# Keg_Cop_-_RJ45.net
KiCad netlist of a schematic drawn in EAGLE
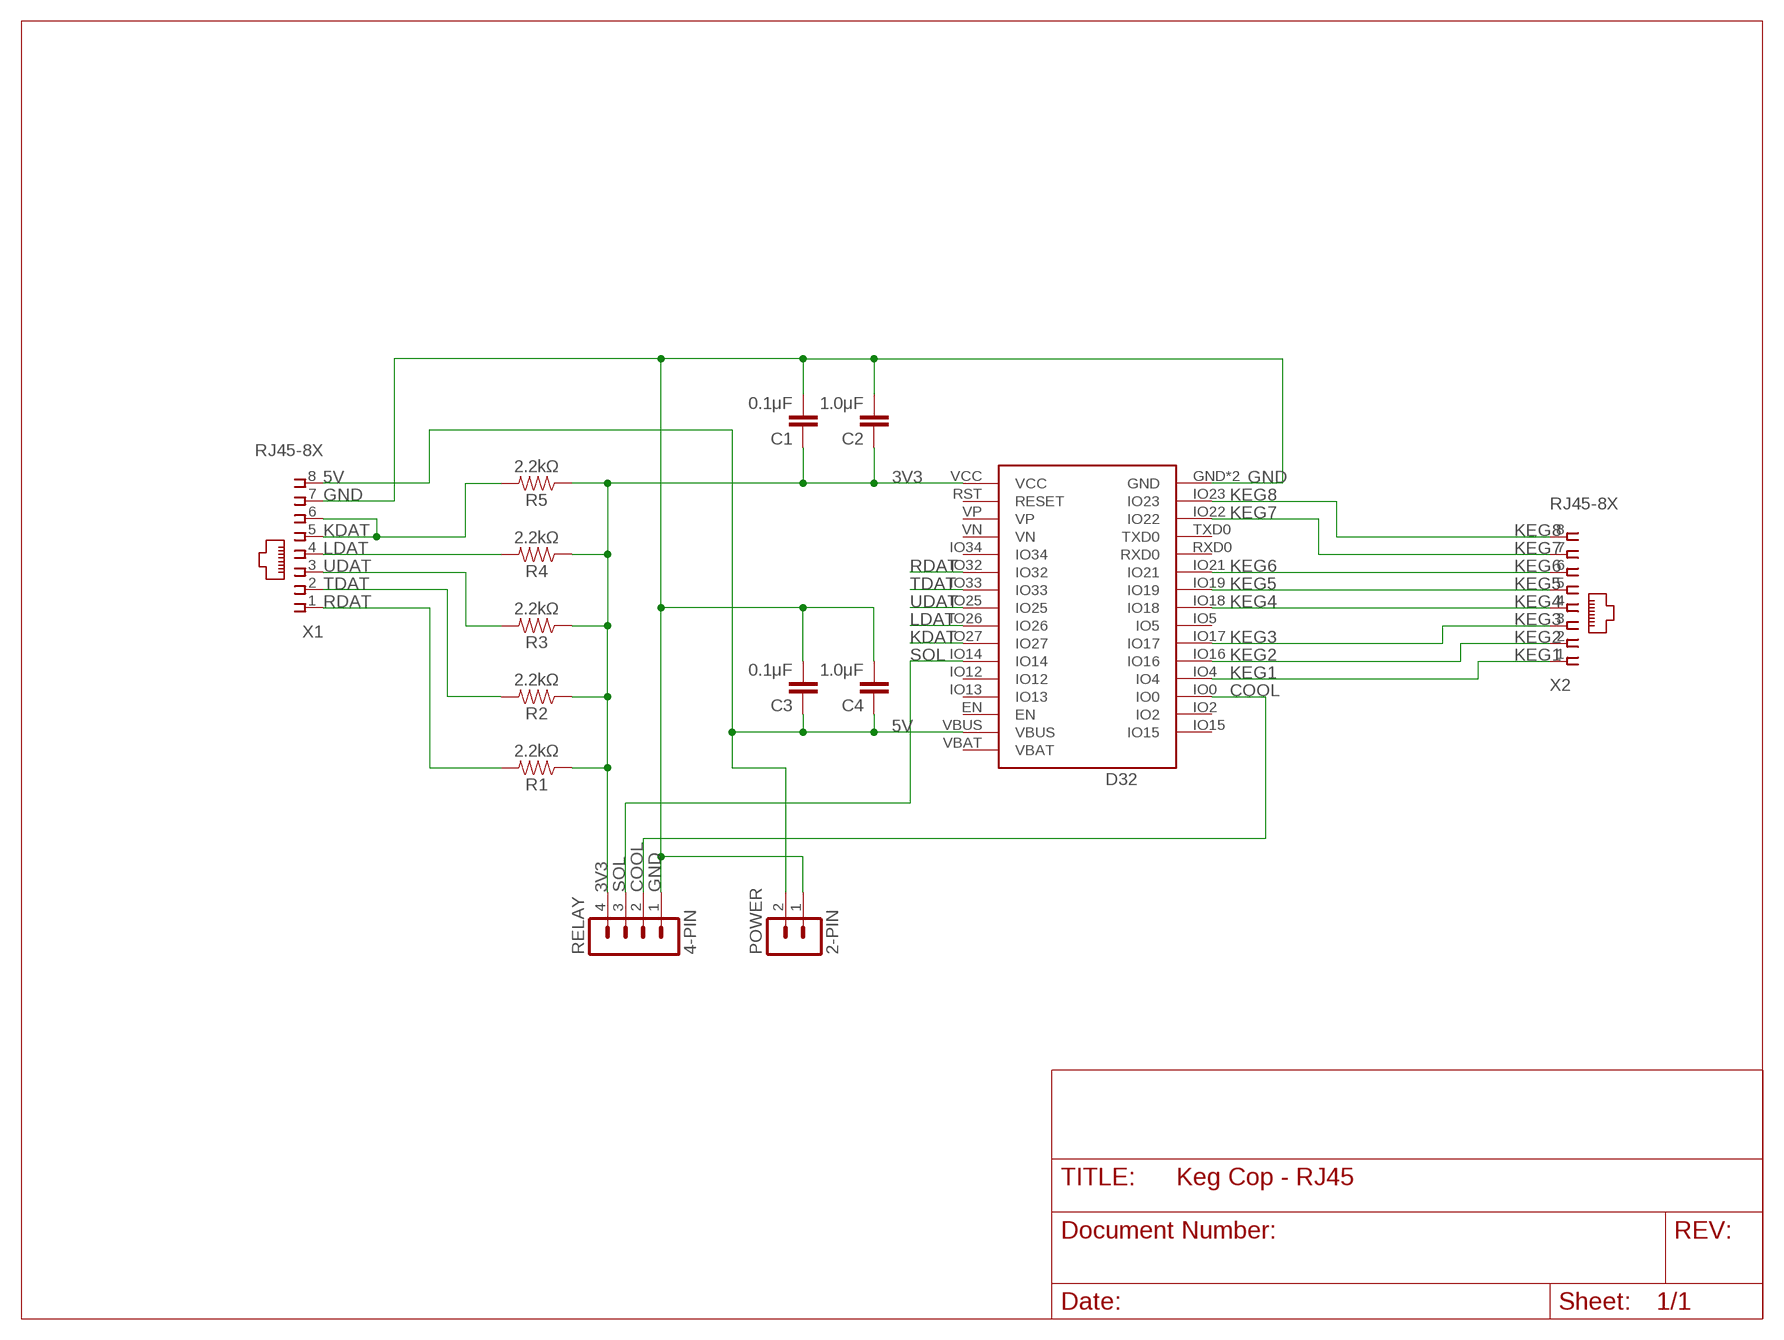
[diagram p0: schematic, sheet 1]

(export (version "E")
  (design (tool "Eeschema 10.0.6"))
  (components
    (comp (ref "C1")
      (value "0.1μF")
      (footprint "eagle-import:CAP_PTH-2.54")
      (libsource (lib "eagle-import") (part "CAP_CERAMIC_2.54"))
    )
    (comp (ref "C2")
      (value "1.0μF")
      (footprint "eagle-import:CAP_PTH-2.54")
      (libsource (lib "eagle-import") (part "CAP_CERAMIC_2.54"))
    )
    (comp (ref "C3")
      (value "0.1μF")
      (footprint "eagle-import:CAP_PTH-2.54")
      (libsource (lib "eagle-import") (part "CAP_CERAMIC_2.54"))
    )
    (comp (ref "C4")
      (value "1.0μF")
      (footprint "eagle-import:CAP_PTH-2.54")
      (libsource (lib "eagle-import") (part "CAP_CERAMIC_2.54"))
    )
    (comp (ref "D32")
      (value "Lolin D32")
      (footprint "eagle-import:D32_NO_BATT")
      (libsource (lib "eagle-import") (part "WEMOS-D32D32_NO_BATT"))
    )
    (comp (ref "POWER")
      (value "2-PIN")
      (footprint "eagle-import:HDR-2_VERT")
      (libsource (lib "eagle-import") (part "HDR-2"))
    )
    (comp (ref "R1")
      (value "2.2kΩ")
      (footprint "eagle-import:AXIAL-0.3")
      (libsource (lib "eagle-import") (part "RESISTORAXIAL-0.3"))
    )
    (comp (ref "R2")
      (value "2.2kΩ")
      (footprint "eagle-import:AXIAL-0.3")
      (libsource (lib "eagle-import") (part "RESISTORAXIAL-0.3"))
    )
    (comp (ref "R3")
      (value "2.2kΩ")
      (footprint "eagle-import:AXIAL-0.3")
      (libsource (lib "eagle-import") (part "RESISTORAXIAL-0.3"))
    )
    (comp (ref "R4")
      (value "2.2kΩ")
      (footprint "eagle-import:AXIAL-0.3")
      (libsource (lib "eagle-import") (part "RESISTORAXIAL-0.3"))
    )
    (comp (ref "R5")
      (value "2.2kΩ")
      (footprint "eagle-import:AXIAL-0.3")
      (libsource (lib "eagle-import") (part "RESISTORAXIAL-0.3"))
    )
    (comp (ref "RELAY")
      (value "4-PIN")
      (footprint "eagle-import:MA04-1")
      (libsource (lib "eagle-import") (part "MA04-1"))
    )
    (comp (ref "X1")
      (value "RJ45-8X")
      (footprint "eagle-import:RJ45-NO-SHIELD")
      (libsource (lib "eagle-import") (part "RJ45-8X"))
    )
    (comp (ref "X2")
      (value "RJ45-8X")
      (footprint "eagle-import:RJ45-NO-SHIELD")
      (libsource (lib "eagle-import") (part "RJ45-8X"))
    )
  )
  (nets
    (net (code "1") (name "/3V3") (class "Default")
      (node (ref "C1") (pin "1") (pinfunction "1_1") (pintype "passive"))
      (node (ref "C2") (pin "1") (pinfunction "1_1") (pintype "passive"))
      (node (ref "D32") (pin "VCC") (pinfunction "VCC_VCC") (pintype "power_in"))
      (node (ref "R1") (pin "P$1") (pinfunction "1_P$1") (pintype "passive"))
      (node (ref "R2") (pin "P$1") (pinfunction "1_P$1") (pintype "passive"))
      (node (ref "R3") (pin "P$1") (pinfunction "1_P$1") (pintype "passive"))
      (node (ref "R4") (pin "P$1") (pinfunction "1_P$1") (pintype "passive"))
      (node (ref "R5") (pin "P$1") (pinfunction "1_P$1") (pintype "passive"))
      (node (ref "RELAY") (pin "4") (pinfunction "4_4") (pintype "passive"))
    )
    (net (code "2") (name "/5V") (class "Default")
      (node (ref "C3") (pin "1") (pinfunction "1_1") (pintype "passive"))
      (node (ref "C4") (pin "1") (pinfunction "1_1") (pintype "passive"))
      (node (ref "D32") (pin "VBUS") (pinfunction "VBUS_VBUS") (pintype "bidirectional"))
      (node (ref "POWER") (pin "2") (pinfunction "2_2") (pintype "passive"))
      (node (ref "X1") (pin "8") (pinfunction "8_8") (pintype "passive"))
    )
    (net (code "3") (name "/COOL") (class "Default")
      (node (ref "D32") (pin "IO0") (pinfunction "IO0_IO0") (pintype "bidirectional"))
      (node (ref "RELAY") (pin "2") (pinfunction "2_2") (pintype "passive"))
    )
    (net (code "4") (name "/GND") (class "Default")
      (node (ref "C1") (pin "2") (pinfunction "2_2") (pintype "passive"))
      (node (ref "C2") (pin "2") (pinfunction "2_2") (pintype "passive"))
      (node (ref "C3") (pin "2") (pinfunction "2_2") (pintype "passive"))
      (node (ref "C4") (pin "2") (pinfunction "2_2") (pintype "passive"))
      (node (ref "D32") (pin "GND") (pinfunction "GND_GND") (pintype "power_in"))
      (node (ref "D32") (pin "GND2") (pinfunction "GND_GND2") (pintype "power_in"))
      (node (ref "POWER") (pin "1") (pinfunction "1_1") (pintype "passive"))
      (node (ref "RELAY") (pin "1") (pinfunction "1_1") (pintype "passive"))
      (node (ref "X1") (pin "7") (pinfunction "7_7") (pintype "passive"))
    )
    (net (code "5") (name "/KDAT") (class "Default")
      (node (ref "D32") (pin "IO27") (pinfunction "IO27_IO27") (pintype "bidirectional"))
      (node (ref "R5") (pin "P$2") (pinfunction "2_P$2") (pintype "passive"))
      (node (ref "X1") (pin "5") (pinfunction "5_5") (pintype "passive"))
      (node (ref "X1") (pin "6") (pinfunction "6_6") (pintype "passive"))
    )
    (net (code "6") (name "/KEG1") (class "Default")
      (node (ref "D32") (pin "IO4") (pinfunction "IO4_IO4") (pintype "bidirectional"))
      (node (ref "X2") (pin "1") (pinfunction "1_1") (pintype "passive"))
    )
    (net (code "7") (name "/KEG2") (class "Default")
      (node (ref "D32") (pin "IO16") (pinfunction "IO16_IO16") (pintype "bidirectional"))
      (node (ref "X2") (pin "2") (pinfunction "2_2") (pintype "passive"))
    )
    (net (code "8") (name "/KEG3") (class "Default")
      (node (ref "D32") (pin "IO17") (pinfunction "IO17_IO17") (pintype "bidirectional"))
      (node (ref "X2") (pin "3") (pinfunction "3_3") (pintype "passive"))
    )
    (net (code "9") (name "/KEG4") (class "Default")
      (node (ref "D32") (pin "IO18") (pinfunction "IO18_IO18") (pintype "bidirectional"))
      (node (ref "X2") (pin "4") (pinfunction "4_4") (pintype "passive"))
    )
    (net (code "10") (name "/KEG5") (class "Default")
      (node (ref "D32") (pin "IO19") (pinfunction "IO19_IO19") (pintype "bidirectional"))
      (node (ref "X2") (pin "5") (pinfunction "5_5") (pintype "passive"))
    )
    (net (code "11") (name "/KEG6") (class "Default")
      (node (ref "D32") (pin "IO21") (pinfunction "IO21_IO21") (pintype "bidirectional"))
      (node (ref "X2") (pin "6") (pinfunction "6_6") (pintype "passive"))
    )
    (net (code "12") (name "/KEG7") (class "Default")
      (node (ref "D32") (pin "IO22") (pinfunction "IO22_IO22") (pintype "bidirectional"))
      (node (ref "X2") (pin "7") (pinfunction "7_7") (pintype "passive"))
    )
    (net (code "13") (name "/KEG8") (class "Default")
      (node (ref "D32") (pin "IO23") (pinfunction "IO23_IO23") (pintype "bidirectional"))
      (node (ref "X2") (pin "8") (pinfunction "8_8") (pintype "passive"))
    )
    (net (code "14") (name "/LDAT") (class "Default")
      (node (ref "D32") (pin "IO26") (pinfunction "IO26_IO26") (pintype "bidirectional"))
      (node (ref "R4") (pin "P$2") (pinfunction "2_P$2") (pintype "passive"))
      (node (ref "X1") (pin "4") (pinfunction "4_4") (pintype "passive"))
    )
    (net (code "15") (name "/RDAT") (class "Default")
      (node (ref "D32") (pin "IO32") (pinfunction "IO32_IO32") (pintype "bidirectional"))
      (node (ref "R1") (pin "P$2") (pinfunction "2_P$2") (pintype "passive"))
      (node (ref "X1") (pin "1") (pinfunction "1_1") (pintype "passive"))
    )
    (net (code "16") (name "/SOL") (class "Default")
      (node (ref "D32") (pin "IO14") (pinfunction "IO14_IO14") (pintype "bidirectional"))
      (node (ref "RELAY") (pin "3") (pinfunction "3_3") (pintype "passive"))
    )
    (net (code "17") (name "/TDAT") (class "Default")
      (node (ref "D32") (pin "IO33") (pinfunction "IO33_IO33") (pintype "bidirectional"))
      (node (ref "R2") (pin "P$2") (pinfunction "2_P$2") (pintype "passive"))
      (node (ref "X1") (pin "2") (pinfunction "2_2") (pintype "passive"))
    )
    (net (code "18") (name "/UDAT") (class "Default")
      (node (ref "D32") (pin "IO25") (pinfunction "IO25_IO25") (pintype "bidirectional"))
      (node (ref "R3") (pin "P$2") (pinfunction "2_P$2") (pintype "passive"))
      (node (ref "X1") (pin "3") (pinfunction "3_3") (pintype "passive"))
    )
    (net (code "19") (name "unconnected-(D32-PadEN)") (class "Default")
      (node (ref "D32") (pin "EN") (pinfunction "EN_EN") (pintype "bidirectional"))
    )
    (net (code "20") (name "unconnected-(D32-PadIO2)") (class "Default")
      (node (ref "D32") (pin "IO2") (pinfunction "IO2_IO2") (pintype "bidirectional"))
    )
    (net (code "21") (name "unconnected-(D32-PadIO5)") (class "Default")
      (node (ref "D32") (pin "IO5") (pinfunction "IO5_IO5") (pintype "bidirectional"))
    )
    (net (code "22") (name "unconnected-(D32-PadIO12)") (class "Default")
      (node (ref "D32") (pin "IO12") (pinfunction "IO12_IO12") (pintype "bidirectional"))
    )
    (net (code "23") (name "unconnected-(D32-PadIO13)") (class "Default")
      (node (ref "D32") (pin "IO13") (pinfunction "IO13_IO13") (pintype "bidirectional"))
    )
    (net (code "24") (name "unconnected-(D32-PadIO15)") (class "Default")
      (node (ref "D32") (pin "IO15") (pinfunction "IO15_IO15") (pintype "bidirectional"))
    )
    (net (code "25") (name "unconnected-(D32-PadIO34)") (class "Default")
      (node (ref "D32") (pin "IO34") (pinfunction "IO34_IO34") (pintype "bidirectional"))
    )
    (net (code "26") (name "unconnected-(D32-PadRXD0)") (class "Default")
      (node (ref "D32") (pin "RXD0") (pinfunction "RXD0_RXD0") (pintype "input"))
    )
    (net (code "27") (name "unconnected-(D32-PadTXD0)") (class "Default")
      (node (ref "D32") (pin "TXD0") (pinfunction "TXD0_TXD0") (pintype "output"))
    )
    (net (code "28") (name "unconnected-(D32-PadVBAT)") (class "Default")
      (node (ref "D32") (pin "VBAT") (pinfunction "VBAT_VBAT") (pintype "bidirectional"))
    )
    (net (code "29") (name "unconnected-(D32-PadVN)") (class "Default")
      (node (ref "D32") (pin "VN") (pinfunction "VN_VN") (pintype "bidirectional"))
    )
    (net (code "30") (name "unconnected-(D32-PadVP)") (class "Default")
      (node (ref "D32") (pin "VP") (pinfunction "VP_VP") (pintype "bidirectional"))
    )
    (net (code "31") (name "unconnected-(D32-RESET-PadRST)") (class "Default")
      (node (ref "D32") (pin "RST") (pinfunction "RESET_RST") (pintype "bidirectional"))
    )
  )
)
